# V1_7_7.net
KiCad netlist of a schematic drawn in EAGLE
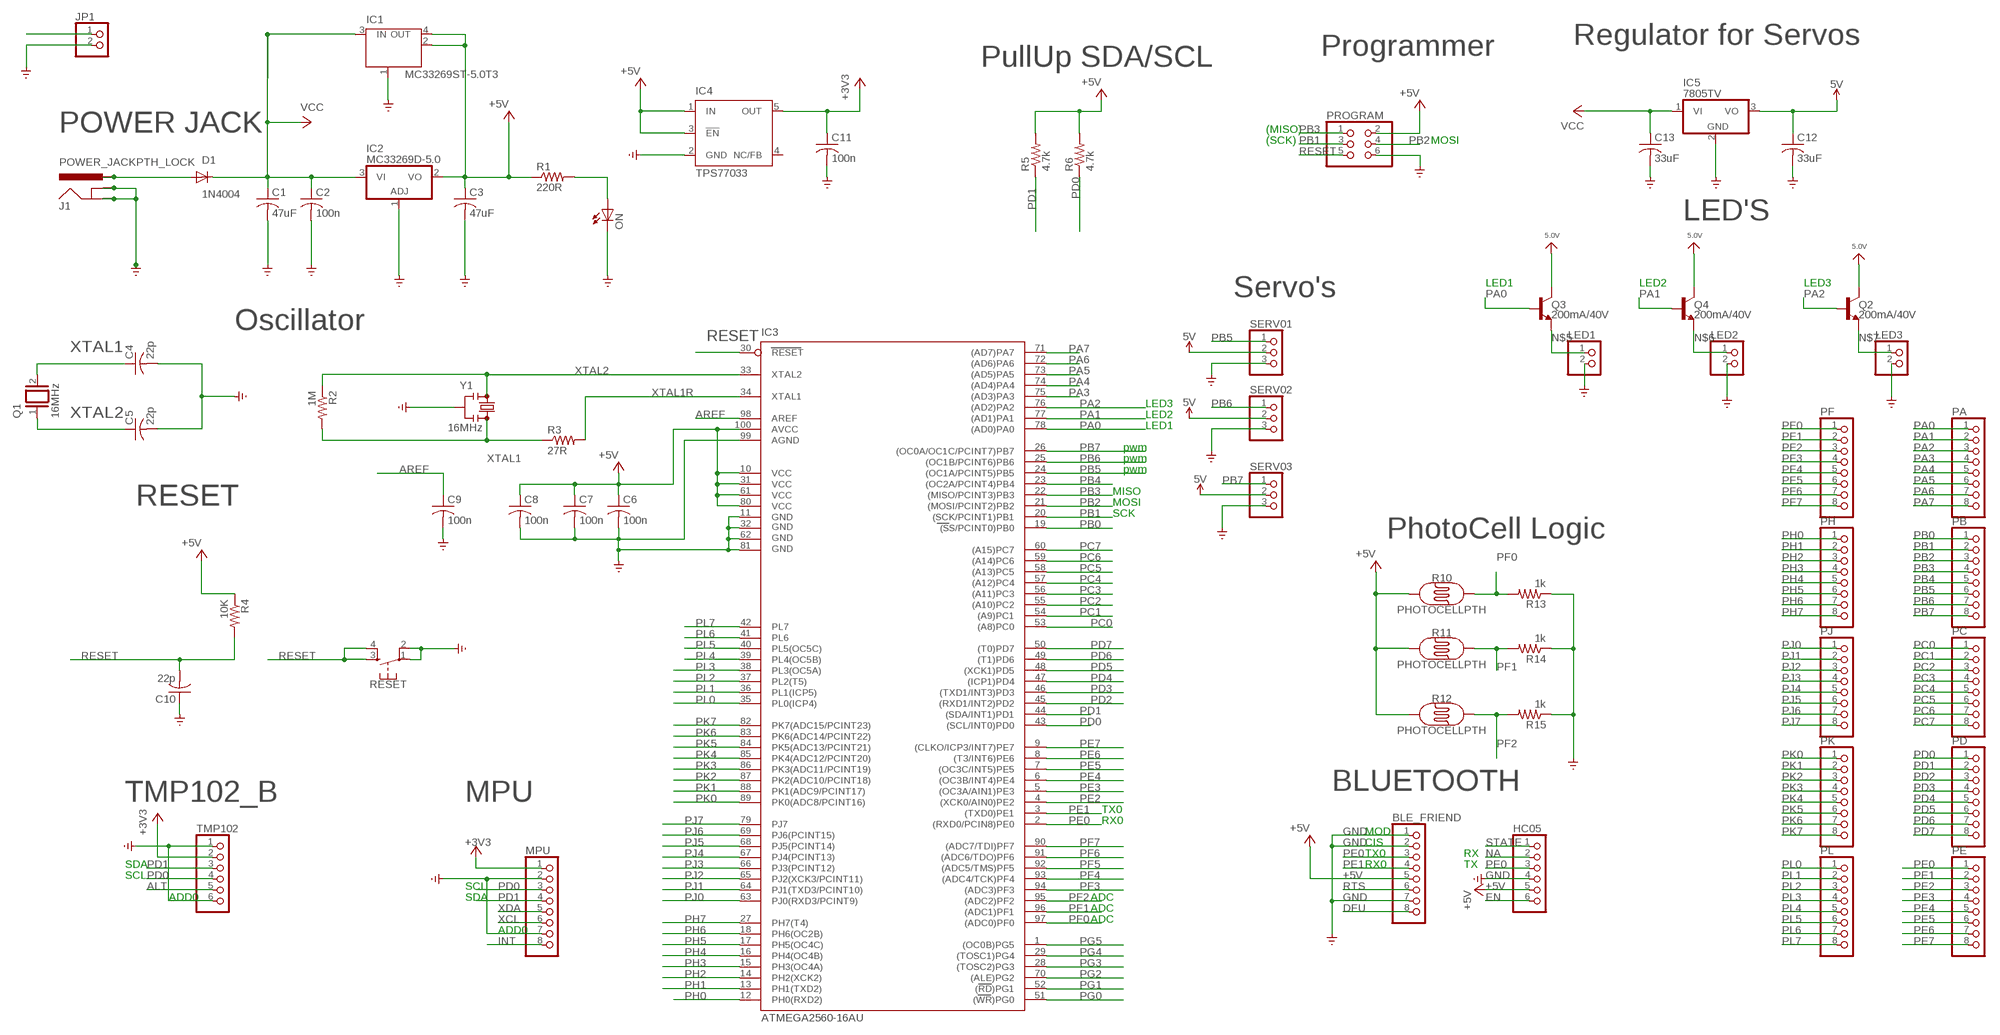
[diagram p0: schematic, sheet 1, part 1 of 2]
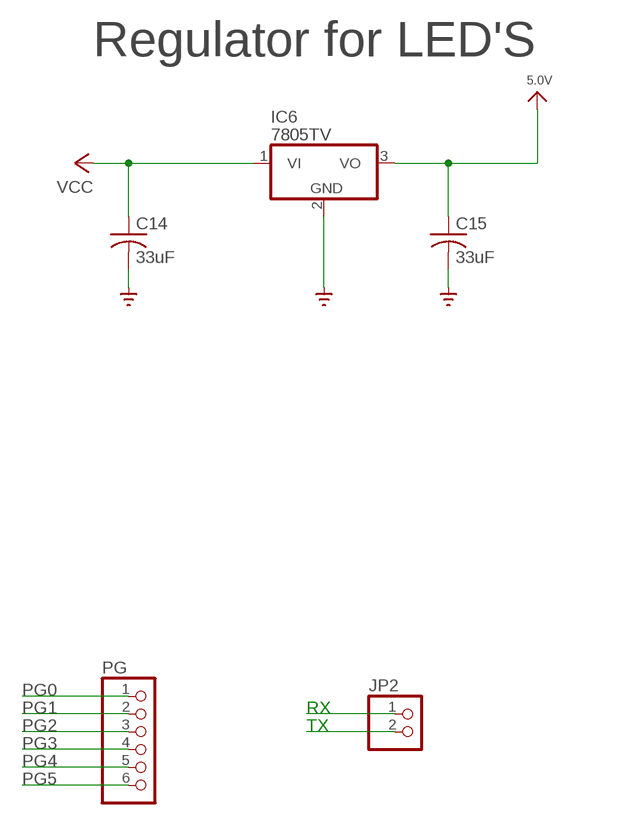
[diagram p1: schematic, sheet 1, part 2 of 2]

(export (version "E")
  (design (tool "Eeschema 10.0.6"))
  (components
    (comp (ref "BLE_FRIEND")
      (value "PINHD-1X8")
      (footprint "eagle-import:1X08")
      (libsource (lib "eagle-import") (part "PINHD-1X8"))
    )
    (comp (ref "C1")
      (value "47uF")
      (footprint "eagle-import:C025-024X044")
      (libsource (lib "eagle-import") (part "C-US025-024X044"))
    )
    (comp (ref "C2")
      (value "100n")
      (footprint "eagle-import:C025-024X044")
      (libsource (lib "eagle-import") (part "C-US025-024X044"))
    )
    (comp (ref "C3")
      (value "47uF")
      (footprint "eagle-import:C025-024X044")
      (libsource (lib "eagle-import") (part "C-US025-024X044"))
    )
    (comp (ref "C4")
      (value "22p")
      (footprint "eagle-import:C025-024X044")
      (libsource (lib "eagle-import") (part "C-US025-024X044"))
    )
    (comp (ref "C5")
      (value "22p")
      (footprint "eagle-import:C025-024X044")
      (libsource (lib "eagle-import") (part "C-US025-024X044"))
    )
    (comp (ref "C6")
      (value "100n")
      (footprint "eagle-import:C025-024X044")
      (libsource (lib "eagle-import") (part "C-US025-024X044"))
    )
    (comp (ref "C7")
      (value "100n")
      (footprint "eagle-import:C025-024X044")
      (libsource (lib "eagle-import") (part "C-US025-024X044"))
    )
    (comp (ref "C8")
      (value "100n")
      (footprint "eagle-import:C025-024X044")
      (libsource (lib "eagle-import") (part "C-US025-024X044"))
    )
    (comp (ref "C9")
      (value "100n")
      (footprint "eagle-import:C025-024X044")
      (libsource (lib "eagle-import") (part "C-US025-024X044"))
    )
    (comp (ref "C10")
      (value "22p")
      (footprint "eagle-import:C025-024X044")
      (libsource (lib "eagle-import") (part "C-US025-024X044"))
    )
    (comp (ref "C11")
      (value "100n")
      (footprint "eagle-import:C025-024X044")
      (libsource (lib "eagle-import") (part "C-US025-024X044"))
    )
    (comp (ref "C12")
      (value "33uF")
      (footprint "eagle-import:C025-024X044")
      (libsource (lib "eagle-import") (part "C-US025-024X044"))
    )
    (comp (ref "C13")
      (value "33uF")
      (footprint "eagle-import:C025-024X044")
      (libsource (lib "eagle-import") (part "C-US025-024X044"))
    )
    (comp (ref "C14")
      (value "33uF")
      (footprint "eagle-import:C025-024X044")
      (libsource (lib "eagle-import") (part "C-US025-024X044"))
    )
    (comp (ref "C15")
      (value "33uF")
      (footprint "eagle-import:C025-024X044")
      (libsource (lib "eagle-import") (part "C-US025-024X044"))
    )
    (comp (ref "D1")
      (value "1N4004")
      (footprint "eagle-import:DO41-10")
      (libsource (lib "eagle-import") (part "1N4004"))
    )
    (comp (ref "HC05")
      (value "PINHD-1X6")
      (footprint "eagle-import:1X06")
      (libsource (lib "eagle-import") (part "pinhead@1_PINHD-1X6"))
    )
    (comp (ref "IC1")
      (value "MC33269ST-5.0T3")
      (footprint "eagle-import:SOT223")
      (libsource (lib "eagle-import") (part "MC33269ST-3.3T3"))
    )
    (comp (ref "IC2")
      (value "MC33269D-5.0")
      (footprint "eagle-import:DPACK")
      (libsource (lib "eagle-import") (part "MC33269?D-5.0"))
    )
    (comp (ref "IC3")
      (value "ATMEGA2560-16AU")
      (footprint "eagle-import:TQFP100")
      (libsource (lib "eagle-import") (part "ATMEGAAU2560-16"))
    )
    (comp (ref "IC4")
      (value "TPS77033")
      (footprint "eagle-import:SOT23-DBV")
      (fields (field (name "MF") "TEXAS INSTRUMENTS") (field (name "MPN") "TPS77033DBVT"))
      (libsource (lib "eagle-import") (part "TPS77033"))
    )
    (comp (ref "IC5")
      (value "7805TV")
      (footprint "eagle-import:TO220V")
      (libsource (lib "eagle-import") (part "78TV05"))
    )
    (comp (ref "IC6")
      (value "7805TV")
      (footprint "eagle-import:TO220V")
      (libsource (lib "eagle-import") (part "78TV05"))
    )
    (comp (ref "J1")
      (value "POWER_JACKPTH_LOCK")
      (footprint "eagle-import:POWER_JACK_PTH_LOCK")
      (libsource (lib "eagle-import") (part "POWER_JACKPTH_LOCK"))
    )
    (comp (ref "JP1")
      (value "PINHD-1X2")
      (footprint "eagle-import:1X02")
      (libsource (lib "eagle-import") (part "PINHD-1X2"))
    )
    (comp (ref "JP2")
      (value "PINHD-1X2")
      (footprint "eagle-import:1X02")
      (libsource (lib "eagle-import") (part "pinhead@1_PINHD-1X2"))
    )
    (comp (ref "LED1")
      (value "PINHD-1X2")
      (footprint "eagle-import:1X02")
      (libsource (lib "eagle-import") (part "PINHD-1X2"))
    )
    (comp (ref "LED2")
      (value "PINHD-1X2")
      (footprint "eagle-import:1X02")
      (libsource (lib "eagle-import") (part "PINHD-1X2"))
    )
    (comp (ref "LED3")
      (value "PINHD-1X2")
      (footprint "eagle-import:1X02")
      (libsource (lib "eagle-import") (part "PINHD-1X2"))
    )
    (comp (ref "MPU")
      (value "PINHD-1X8")
      (footprint "eagle-import:1X08")
      (libsource (lib "eagle-import") (part "PINHD-1X8"))
    )
    (comp (ref "ON")
      (value "LED3MM")
      (footprint "eagle-import:LED3MM")
      (libsource (lib "eagle-import") (part "LED3MM"))
    )
    (comp (ref "PA")
      (value "PINHD-1X8")
      (footprint "eagle-import:1X08")
      (libsource (lib "eagle-import") (part "PINHD-1X8"))
    )
    (comp (ref "PB")
      (value "PINHD-1X8")
      (footprint "eagle-import:1X08")
      (libsource (lib "eagle-import") (part "PINHD-1X8"))
    )
    (comp (ref "PC")
      (value "PINHD-1X8")
      (footprint "eagle-import:1X08")
      (libsource (lib "eagle-import") (part "PINHD-1X8"))
    )
    (comp (ref "PD")
      (value "PINHD-1X8")
      (footprint "eagle-import:1X08")
      (libsource (lib "eagle-import") (part "PINHD-1X8"))
    )
    (comp (ref "PE")
      (value "PINHD-1X8")
      (footprint "eagle-import:1X08")
      (libsource (lib "eagle-import") (part "PINHD-1X8"))
    )
    (comp (ref "PF")
      (value "PINHD-1X8")
      (footprint "eagle-import:1X08")
      (libsource (lib "eagle-import") (part "PINHD-1X8"))
    )
    (comp (ref "PG")
      (value "PINHD-1X6")
      (footprint "eagle-import:1X06")
      (libsource (lib "eagle-import") (part "PINHD-1X6"))
    )
    (comp (ref "PH")
      (value "PINHD-1X8")
      (footprint "eagle-import:1X08")
      (libsource (lib "eagle-import") (part "PINHD-1X8"))
    )
    (comp (ref "PJ")
      (value "PINHD-1X8")
      (footprint "eagle-import:1X08")
      (libsource (lib "eagle-import") (part "PINHD-1X8"))
    )
    (comp (ref "PK")
      (value "PINHD-1X8")
      (footprint "eagle-import:1X08")
      (libsource (lib "eagle-import") (part "PINHD-1X8"))
    )
    (comp (ref "PL")
      (value "PINHD-1X8")
      (footprint "eagle-import:1X08")
      (libsource (lib "eagle-import") (part "PINHD-1X8"))
    )
    (comp (ref "PROGRAM")
      (value "PINHD-2X3")
      (footprint "eagle-import:2X03")
      (libsource (lib "eagle-import") (part "PINHD-2X3"))
    )
    (comp (ref "Q1")
      (value "16MHz")
      (footprint "eagle-import:QS")
      (libsource (lib "eagle-import") (part "XTAL/S"))
    )
    (comp (ref "Q2")
      (value "200mA/40V")
      (footprint "eagle-import:TO-92")
      (libsource (lib "eagle-import") (part "TRANS_NPN-2N3904"))
    )
    (comp (ref "Q3")
      (value "200mA/40V")
      (footprint "eagle-import:TO-92")
      (libsource (lib "eagle-import") (part "TRANS_NPN-2N3904"))
    )
    (comp (ref "Q4")
      (value "200mA/40V")
      (footprint "eagle-import:TO-92")
      (libsource (lib "eagle-import") (part "TRANS_NPN-2N3904"))
    )
    (comp (ref "R1")
      (value "220R")
      (footprint "eagle-import:0204V")
      (libsource (lib "eagle-import") (part "R-US_0204/2V"))
    )
    (comp (ref "R2")
      (value "1M")
      (footprint "eagle-import:0204V")
      (libsource (lib "eagle-import") (part "R-US_0204/2V"))
    )
    (comp (ref "R3")
      (value "27R")
      (footprint "eagle-import:0204V")
      (libsource (lib "eagle-import") (part "R-US_0204/2V"))
    )
    (comp (ref "R4")
      (value "10K")
      (footprint "eagle-import:0204V")
      (libsource (lib "eagle-import") (part "R-US_0204/2V"))
    )
    (comp (ref "R5")
      (value "4.7k")
      (footprint "eagle-import:0204V")
      (libsource (lib "eagle-import") (part "R-US_0204/2V"))
    )
    (comp (ref "R6")
      (value "4.7k")
      (footprint "eagle-import:0204V")
      (libsource (lib "eagle-import") (part "R-US_0204/2V"))
    )
    (comp (ref "R10")
      (value "PHOTOCELLPTH")
      (footprint "eagle-import:PHOTOCELL")
      (libsource (lib "eagle-import") (part "PHOTOCELLPTH"))
    )
    (comp (ref "R11")
      (value "PHOTOCELLPTH")
      (footprint "eagle-import:PHOTOCELL")
      (libsource (lib "eagle-import") (part "PHOTOCELLPTH"))
    )
    (comp (ref "R12")
      (value "PHOTOCELLPTH")
      (footprint "eagle-import:PHOTOCELL")
      (libsource (lib "eagle-import") (part "PHOTOCELLPTH"))
    )
    (comp (ref "R13")
      (value "1k")
      (footprint "eagle-import:0204V")
      (libsource (lib "eagle-import") (part "R-US_0204/2V"))
    )
    (comp (ref "R14")
      (value "1k")
      (footprint "eagle-import:0204V")
      (libsource (lib "eagle-import") (part "R-US_0204/2V"))
    )
    (comp (ref "R15")
      (value "1k")
      (footprint "eagle-import:0204V")
      (libsource (lib "eagle-import") (part "R-US_0204/2V"))
    )
    (comp (ref "RESET")
      (value "MOMENTARY-SWITCH-SPST-2-SMD-5.2MM")
      (footprint "eagle-import:TACTILE_SWITCH_SMD_5.2MM")
      (libsource (lib "eagle-import") (part "MOMENTARY-SWITCH-SPST-2-SMD-5.2MM"))
    )
    (comp (ref "SERV01")
      (value "PINHD-1X3")
      (footprint "eagle-import:1X03")
      (libsource (lib "eagle-import") (part "PINHD-1X3"))
    )
    (comp (ref "SERV02")
      (value "PINHD-1X3")
      (footprint "eagle-import:1X03")
      (libsource (lib "eagle-import") (part "PINHD-1X3"))
    )
    (comp (ref "SERV03")
      (value "PINHD-1X3")
      (footprint "eagle-import:1X03")
      (libsource (lib "eagle-import") (part "PINHD-1X3"))
    )
    (comp (ref "TMP102")
      (value "PINHD-1X6")
      (footprint "eagle-import:1X06")
      (libsource (lib "eagle-import") (part "PINHD-1X6"))
    )
    (comp (ref "Y1")
      (value "16MHz")
      (footprint "eagle-import:RESONATOR-SMD-3.2X1.3")
      (libsource (lib "eagle-import") (part "RESONATORSMD-3.2X1.3"))
    )
  )
  (nets
    (net (code "1") (name "+3V3") (class "Default")
      (node (ref "C11") (pin "1") (pinfunction "1_1") (pintype "passive"))
      (node (ref "IC4") (pin "5") (pinfunction "OUT_5") (pintype "passive"))
      (node (ref "MPU") (pin "1") (pinfunction "1_1") (pintype "passive"))
      (node (ref "TMP102") (pin "2") (pinfunction "2_2") (pintype "passive"))
    )
    (net (code "2") (name "+5V") (class "Default")
      (node (ref "BLE_FRIEND") (pin "5") (pinfunction "5_5") (pintype "passive"))
      (node (ref "C3") (pin "1") (pinfunction "1_1") (pintype "passive"))
      (node (ref "C6") (pin "1") (pinfunction "1_1") (pintype "passive"))
      (node (ref "C7") (pin "1") (pinfunction "1_1") (pintype "passive"))
      (node (ref "C8") (pin "1") (pinfunction "1_1") (pintype "passive"))
      (node (ref "HC05") (pin "5") (pinfunction "5_5") (pintype "passive"))
      (node (ref "IC1") (pin "2") (pinfunction "OUT_2") (pintype "passive"))
      (node (ref "IC1") (pin "4") (pinfunction "OUT_4") (pintype "passive"))
      (node (ref "IC2") (pin "2") (pinfunction "VO_2") (pintype "passive"))
      (node (ref "IC3") (pin "10") (pinfunction "VCC_10") (pintype "power_in"))
      (node (ref "IC3") (pin "100") (pinfunction "AVCC_100") (pintype "power_in"))
      (node (ref "IC3") (pin "31") (pinfunction "VCC1_31") (pintype "power_in"))
      (node (ref "IC3") (pin "61") (pinfunction "VCC2_61") (pintype "power_in"))
      (node (ref "IC3") (pin "80") (pinfunction "VCC3_80") (pintype "power_in"))
      (node (ref "IC4") (pin "1") (pinfunction "IN_1") (pintype "input"))
      (node (ref "IC4") (pin "3") (pinfunction "~{EN}_3") (pintype "input"))
      (node (ref "PROGRAM") (pin "2") (pinfunction "2_2") (pintype "passive"))
      (node (ref "R1") (pin "1") (pinfunction "1_1") (pintype "passive"))
      (node (ref "R10") (pin "1") (pinfunction "P$1_1") (pintype "bidirectional"))
      (node (ref "R11") (pin "1") (pinfunction "P$1_1") (pintype "bidirectional"))
      (node (ref "R12") (pin "1") (pinfunction "P$1_1") (pintype "bidirectional"))
      (node (ref "R4") (pin "1") (pinfunction "1_1") (pintype "passive"))
      (node (ref "R5") (pin "2") (pinfunction "2_2") (pintype "passive"))
      (node (ref "R6") (pin "2") (pinfunction "2_2") (pintype "passive"))
    )
    (net (code "3") (name "/ALT") (class "Default")
      (node (ref "TMP102") (pin "5") (pinfunction "5_5") (pintype "passive"))
    )
    (net (code "4") (name "/AREF") (class "Default")
      (node (ref "C9") (pin "1") (pinfunction "1_1") (pintype "passive"))
      (node (ref "IC3") (pin "98") (pinfunction "AREF_98") (pintype "bidirectional"))
    )
    (net (code "5") (name "/DFU") (class "Default")
      (node (ref "BLE_FRIEND") (pin "8") (pinfunction "8_8") (pintype "passive"))
    )
    (net (code "6") (name "/EN") (class "Default")
      (node (ref "HC05") (pin "6") (pinfunction "6_6") (pintype "passive"))
    )
    (net (code "7") (name "/INT") (class "Default")
      (node (ref "MPU") (pin "8") (pinfunction "8_8") (pintype "passive"))
    )
    (net (code "8") (name "/N$5") (class "Default")
      (node (ref "LED1") (pin "1") (pinfunction "1_1") (pintype "passive"))
      (node (ref "Q3") (pin "1") (pinfunction "E_1") (pintype "passive"))
    )
    (net (code "9") (name "/N$6") (class "Default")
      (node (ref "LED2") (pin "1") (pinfunction "1_1") (pintype "passive"))
      (node (ref "Q4") (pin "1") (pinfunction "E_1") (pintype "passive"))
    )
    (net (code "10") (name "/N$7") (class "Default")
      (node (ref "LED3") (pin "1") (pinfunction "1_1") (pintype "passive"))
      (node (ref "Q2") (pin "1") (pinfunction "E_1") (pintype "passive"))
    )
    (net (code "11") (name "/NA") (class "Default")
      (node (ref "HC05") (pin "2") (pinfunction "2_2") (pintype "passive"))
    )
    (net (code "12") (name "/PA0") (class "Default")
      (node (ref "IC3") (pin "78") (pinfunction "(AD0)PA0_78") (pintype "bidirectional"))
      (node (ref "PA") (pin "1") (pinfunction "1_1") (pintype "passive"))
      (node (ref "Q3") (pin "2") (pinfunction "B_2") (pintype "passive"))
    )
    (net (code "13") (name "/PA1") (class "Default")
      (node (ref "IC3") (pin "77") (pinfunction "(AD1)PA1_77") (pintype "bidirectional"))
      (node (ref "PA") (pin "2") (pinfunction "2_2") (pintype "passive"))
      (node (ref "Q4") (pin "2") (pinfunction "B_2") (pintype "passive"))
    )
    (net (code "14") (name "/PA2") (class "Default")
      (node (ref "IC3") (pin "76") (pinfunction "(AD2)PA2_76") (pintype "bidirectional"))
      (node (ref "PA") (pin "3") (pinfunction "3_3") (pintype "passive"))
      (node (ref "Q2") (pin "2") (pinfunction "B_2") (pintype "passive"))
    )
    (net (code "15") (name "/PA3") (class "Default")
      (node (ref "IC3") (pin "75") (pinfunction "(AD3)PA3_75") (pintype "bidirectional"))
      (node (ref "PA") (pin "4") (pinfunction "4_4") (pintype "passive"))
    )
    (net (code "16") (name "/PA4") (class "Default")
      (node (ref "IC3") (pin "74") (pinfunction "(AD4)PA4_74") (pintype "bidirectional"))
      (node (ref "PA") (pin "5") (pinfunction "5_5") (pintype "passive"))
    )
    (net (code "17") (name "/PA5") (class "Default")
      (node (ref "IC3") (pin "73") (pinfunction "(AD5)PA5_73") (pintype "bidirectional"))
      (node (ref "PA") (pin "6") (pinfunction "6_6") (pintype "passive"))
    )
    (net (code "18") (name "/PA6") (class "Default")
      (node (ref "IC3") (pin "72") (pinfunction "(AD6)PA6_72") (pintype "bidirectional"))
      (node (ref "PA") (pin "7") (pinfunction "7_7") (pintype "passive"))
    )
    (net (code "19") (name "/PA7") (class "Default")
      (node (ref "IC3") (pin "71") (pinfunction "(AD7)PA7_71") (pintype "bidirectional"))
      (node (ref "PA") (pin "8") (pinfunction "8_8") (pintype "passive"))
    )
    (net (code "20") (name "/PB0") (class "Default")
      (node (ref "IC3") (pin "19") (pinfunction "(SS/PCINT0)PB0_19") (pintype "bidirectional"))
      (node (ref "PB") (pin "1") (pinfunction "1_1") (pintype "passive"))
    )
    (net (code "21") (name "/PB1") (class "Default")
      (node (ref "IC3") (pin "20") (pinfunction "(SCK/PCINT1)PB1_20") (pintype "bidirectional"))
      (node (ref "PB") (pin "2") (pinfunction "2_2") (pintype "passive"))
      (node (ref "PROGRAM") (pin "3") (pinfunction "3_3") (pintype "passive"))
    )
    (net (code "22") (name "/PB2") (class "Default")
      (node (ref "IC3") (pin "21") (pinfunction "(MOSI/PCINT2)PB2_21") (pintype "bidirectional"))
      (node (ref "PB") (pin "3") (pinfunction "3_3") (pintype "passive"))
      (node (ref "PROGRAM") (pin "4") (pinfunction "4_4") (pintype "passive"))
    )
    (net (code "23") (name "/PB3") (class "Default")
      (node (ref "IC3") (pin "22") (pinfunction "(MISO/PCINT3)PB3_22") (pintype "bidirectional"))
      (node (ref "PB") (pin "4") (pinfunction "4_4") (pintype "passive"))
      (node (ref "PROGRAM") (pin "1") (pinfunction "1_1") (pintype "passive"))
    )
    (net (code "24") (name "/PB4") (class "Default")
      (node (ref "IC3") (pin "23") (pinfunction "(OC2A/PCINT4)PB4_23") (pintype "bidirectional"))
      (node (ref "PB") (pin "5") (pinfunction "5_5") (pintype "passive"))
    )
    (net (code "25") (name "/PB5") (class "Default")
      (node (ref "IC3") (pin "24") (pinfunction "(OC1A/PCINT5)PB5_24") (pintype "bidirectional"))
      (node (ref "PB") (pin "6") (pinfunction "6_6") (pintype "passive"))
      (node (ref "SERV01") (pin "1") (pinfunction "1_1") (pintype "passive"))
    )
    (net (code "26") (name "/PB6") (class "Default")
      (node (ref "IC3") (pin "25") (pinfunction "(OC1B/PCINT6)PB6_25") (pintype "bidirectional"))
      (node (ref "PB") (pin "7") (pinfunction "7_7") (pintype "passive"))
      (node (ref "SERV02") (pin "1") (pinfunction "1_1") (pintype "passive"))
    )
    (net (code "27") (name "/PB7") (class "Default")
      (node (ref "IC3") (pin "26") (pinfunction "(OC0A/OC1C/PCINT7)PB7_26") (pintype "bidirectional"))
      (node (ref "PB") (pin "8") (pinfunction "8_8") (pintype "passive"))
      (node (ref "SERV03") (pin "1") (pinfunction "1_1") (pintype "passive"))
    )
    (net (code "28") (name "/PC0") (class "Default")
      (node (ref "IC3") (pin "53") (pinfunction "(A8)PC0_53") (pintype "bidirectional"))
      (node (ref "PC") (pin "1") (pinfunction "1_1") (pintype "passive"))
    )
    (net (code "29") (name "/PC1") (class "Default")
      (node (ref "IC3") (pin "54") (pinfunction "(A9)PC1_54") (pintype "bidirectional"))
      (node (ref "PC") (pin "2") (pinfunction "2_2") (pintype "passive"))
    )
    (net (code "30") (name "/PC2") (class "Default")
      (node (ref "IC3") (pin "55") (pinfunction "(A10)PC2_55") (pintype "bidirectional"))
      (node (ref "PC") (pin "3") (pinfunction "3_3") (pintype "passive"))
    )
    (net (code "31") (name "/PC3") (class "Default")
      (node (ref "IC3") (pin "56") (pinfunction "(A11)PC3_56") (pintype "bidirectional"))
      (node (ref "PC") (pin "4") (pinfunction "4_4") (pintype "passive"))
    )
    (net (code "32") (name "/PC4") (class "Default")
      (node (ref "IC3") (pin "57") (pinfunction "(A12)PC4_57") (pintype "bidirectional"))
      (node (ref "PC") (pin "5") (pinfunction "5_5") (pintype "passive"))
    )
    (net (code "33") (name "/PC5") (class "Default")
      (node (ref "IC3") (pin "58") (pinfunction "(A13)PC5_58") (pintype "bidirectional"))
      (node (ref "PC") (pin "6") (pinfunction "6_6") (pintype "passive"))
    )
    (net (code "34") (name "/PC6") (class "Default")
      (node (ref "IC3") (pin "59") (pinfunction "(A14)PC6_59") (pintype "bidirectional"))
      (node (ref "PC") (pin "7") (pinfunction "7_7") (pintype "passive"))
    )
    (net (code "35") (name "/PC7") (class "Default")
      (node (ref "IC3") (pin "60") (pinfunction "(A15)PC7_60") (pintype "bidirectional"))
      (node (ref "PC") (pin "8") (pinfunction "8_8") (pintype "passive"))
    )
    (net (code "36") (name "/PD0") (class "Default")
      (node (ref "IC3") (pin "43") (pinfunction "(SCL/INT0)PD0_43") (pintype "bidirectional"))
      (node (ref "MPU") (pin "3") (pinfunction "3_3") (pintype "passive"))
      (node (ref "PD") (pin "1") (pinfunction "1_1") (pintype "passive"))
      (node (ref "R6") (pin "1") (pinfunction "1_1") (pintype "passive"))
      (node (ref "TMP102") (pin "4") (pinfunction "4_4") (pintype "passive"))
    )
    (net (code "37") (name "/PD1") (class "Default")
      (node (ref "IC3") (pin "44") (pinfunction "(SDA/INT1)PD1_44") (pintype "bidirectional"))
      (node (ref "MPU") (pin "4") (pinfunction "4_4") (pintype "passive"))
      (node (ref "PD") (pin "2") (pinfunction "2_2") (pintype "passive"))
      (node (ref "R5") (pin "1") (pinfunction "1_1") (pintype "passive"))
      (node (ref "TMP102") (pin "3") (pinfunction "3_3") (pintype "passive"))
    )
    (net (code "38") (name "/PD2") (class "Default")
      (node (ref "IC3") (pin "45") (pinfunction "(RXD1/INT2)PD2_45") (pintype "bidirectional"))
      (node (ref "PD") (pin "3") (pinfunction "3_3") (pintype "passive"))
    )
    (net (code "39") (name "/PD3") (class "Default")
      (node (ref "IC3") (pin "46") (pinfunction "(TXD1/INT3)PD3_46") (pintype "bidirectional"))
      (node (ref "PD") (pin "4") (pinfunction "4_4") (pintype "passive"))
    )
    (net (code "40") (name "/PD4") (class "Default")
      (node (ref "IC3") (pin "47") (pinfunction "(ICP1)PD4_47") (pintype "bidirectional"))
      (node (ref "PD") (pin "5") (pinfunction "5_5") (pintype "passive"))
    )
    (net (code "41") (name "/PD5") (class "Default")
      (node (ref "IC3") (pin "48") (pinfunction "(XCK1)PD5_48") (pintype "bidirectional"))
      (node (ref "PD") (pin "6") (pinfunction "6_6") (pintype "passive"))
    )
    (net (code "42") (name "/PD6") (class "Default")
      (node (ref "IC3") (pin "49") (pinfunction "(T1)PD6_49") (pintype "bidirectional"))
      (node (ref "PD") (pin "7") (pinfunction "7_7") (pintype "passive"))
    )
    (net (code "43") (name "/PD7") (class "Default")
      (node (ref "IC3") (pin "50") (pinfunction "(T0)PD7_50") (pintype "bidirectional"))
      (node (ref "PD") (pin "8") (pinfunction "8_8") (pintype "passive"))
    )
    (net (code "44") (name "/PE0") (class "Default")
      (node (ref "BLE_FRIEND") (pin "3") (pinfunction "3_3") (pintype "passive"))
      (node (ref "HC05") (pin "3") (pinfunction "3_3") (pintype "passive"))
      (node (ref "IC3") (pin "2") (pinfunction "(RXD0/PCIN8)PE0_2") (pintype "bidirectional"))
      (node (ref "JP2") (pin "1") (pinfunction "1_1") (pintype "passive"))
      (node (ref "PE") (pin "1") (pinfunction "1_1") (pintype "passive"))
    )
    (net (code "45") (name "/PE1") (class "Default")
      (node (ref "BLE_FRIEND") (pin "4") (pinfunction "4_4") (pintype "passive"))
      (node (ref "IC3") (pin "3") (pinfunction "(TXD0)PE1_3") (pintype "bidirectional"))
      (node (ref "JP2") (pin "2") (pinfunction "2_2") (pintype "passive"))
      (node (ref "PE") (pin "2") (pinfunction "2_2") (pintype "passive"))
    )
    (net (code "46") (name "/PE2") (class "Default")
      (node (ref "IC3") (pin "4") (pinfunction "(XCK0/AIN0)PE2_4") (pintype "bidirectional"))
      (node (ref "PE") (pin "3") (pinfunction "3_3") (pintype "passive"))
    )
    (net (code "47") (name "/PE3") (class "Default")
      (node (ref "IC3") (pin "5") (pinfunction "(OC3A/AIN1)PE3_5") (pintype "bidirectional"))
      (node (ref "PE") (pin "4") (pinfunction "4_4") (pintype "passive"))
    )
    (net (code "48") (name "/PE4") (class "Default")
      (node (ref "IC3") (pin "6") (pinfunction "(OC3B/INT4)PE4_6") (pintype "bidirectional"))
      (node (ref "PE") (pin "5") (pinfunction "5_5") (pintype "passive"))
    )
    (net (code "49") (name "/PE5") (class "Default")
      (node (ref "IC3") (pin "7") (pinfunction "(OC3C/INT5)PE5_7") (pintype "bidirectional"))
      (node (ref "PE") (pin "6") (pinfunction "6_6") (pintype "passive"))
    )
    (net (code "50") (name "/PE6") (class "Default")
      (node (ref "IC3") (pin "8") (pinfunction "(T3/INT6)PE6_8") (pintype "bidirectional"))
      (node (ref "PE") (pin "7") (pinfunction "7_7") (pintype "passive"))
    )
    (net (code "51") (name "/PE7") (class "Default")
      (node (ref "IC3") (pin "9") (pinfunction "(CLKO/ICP3/INT7)PE7_9") (pintype "bidirectional"))
      (node (ref "PE") (pin "8") (pinfunction "8_8") (pintype "passive"))
    )
    (net (code "52") (name "/PF0") (class "Default")
      (node (ref "IC3") (pin "97") (pinfunction "(ADC0)PF0_97") (pintype "bidirectional"))
      (node (ref "PF") (pin "1") (pinfunction "1_1") (pintype "passive"))
      (node (ref "R10") (pin "2") (pinfunction "P$2_2") (pintype "bidirectional"))
      (node (ref "R13") (pin "2") (pinfunction "2_2") (pintype "passive"))
    )
    (net (code "53") (name "/PF1") (class "Default")
      (node (ref "IC3") (pin "96") (pinfunction "(ADC1)PF1_96") (pintype "bidirectional"))
      (node (ref "PF") (pin "2") (pinfunction "2_2") (pintype "passive"))
      (node (ref "R11") (pin "2") (pinfunction "P$2_2") (pintype "bidirectional"))
      (node (ref "R14") (pin "2") (pinfunction "2_2") (pintype "passive"))
    )
    (net (code "54") (name "/PF2") (class "Default")
      (node (ref "IC3") (pin "95") (pinfunction "(ADC2)PF2_95") (pintype "bidirectional"))
      (node (ref "PF") (pin "3") (pinfunction "3_3") (pintype "passive"))
      (node (ref "R12") (pin "2") (pinfunction "P$2_2") (pintype "bidirectional"))
      (node (ref "R15") (pin "2") (pinfunction "2_2") (pintype "passive"))
    )
    (net (code "55") (name "/PF3") (class "Default")
      (node (ref "IC3") (pin "94") (pinfunction "(ADC3)PF3_94") (pintype "bidirectional"))
      (node (ref "PF") (pin "4") (pinfunction "4_4") (pintype "passive"))
    )
    (net (code "56") (name "/PF4") (class "Default")
      (node (ref "IC3") (pin "93") (pinfunction "(ADC4/TCK)PF4_93") (pintype "bidirectional"))
      (node (ref "PF") (pin "5") (pinfunction "5_5") (pintype "passive"))
    )
    (net (code "57") (name "/PF5") (class "Default")
      (node (ref "IC3") (pin "92") (pinfunction "(ADC5/TMS)PF5_92") (pintype "bidirectional"))
      (node (ref "PF") (pin "6") (pinfunction "6_6") (pintype "passive"))
    )
    (net (code "58") (name "/PF6") (class "Default")
      (node (ref "IC3") (pin "91") (pinfunction "(ADC6/TDO)PF6_91") (pintype "bidirectional"))
      (node (ref "PF") (pin "7") (pinfunction "7_7") (pintype "passive"))
    )
    (net (code "59") (name "/PF7") (class "Default")
      (node (ref "IC3") (pin "90") (pinfunction "(ADC7/TDI)PF7_90") (pintype "bidirectional"))
      (node (ref "PF") (pin "8") (pinfunction "8_8") (pintype "passive"))
    )
    (net (code "60") (name "/PG0") (class "Default")
      (node (ref "IC3") (pin "51") (pinfunction "(WR)PG0_51") (pintype "bidirectional"))
      (node (ref "PG") (pin "1") (pinfunction "1_1") (pintype "passive"))
    )
    (net (code "61") (name "/PG1") (class "Default")
      (node (ref "IC3") (pin "52") (pinfunction "(RD)PG1_52") (pintype "bidirectional"))
      (node (ref "PG") (pin "2") (pinfunction "2_2") (pintype "passive"))
    )
    (net (code "62") (name "/PG2") (class "Default")
      (node (ref "IC3") (pin "70") (pinfunction "(ALE)PG2_70") (pintype "bidirectional"))
      (node (ref "PG") (pin "3") (pinfunction "3_3") (pintype "passive"))
    )
    (net (code "63") (name "/PG3") (class "Default")
      (node (ref "IC3") (pin "28") (pinfunction "(TOSC2)PG3_28") (pintype "bidirectional"))
      (node (ref "PG") (pin "4") (pinfunction "4_4") (pintype "passive"))
    )
    (net (code "64") (name "/PG4") (class "Default")
      (node (ref "IC3") (pin "29") (pinfunction "(TOSC1)PG4_29") (pintype "bidirectional"))
      (node (ref "PG") (pin "5") (pinfunction "5_5") (pintype "passive"))
    )
    (net (code "65") (name "/PG5") (class "Default")
      (node (ref "IC3") (pin "1") (pinfunction "(OC0B)PG5_1") (pintype "bidirectional"))
      (node (ref "PG") (pin "6") (pinfunction "6_6") (pintype "passive"))
    )
    (net (code "66") (name "/PH0") (class "Default")
      (node (ref "IC3") (pin "12") (pinfunction "PH0(RXD2)_12") (pintype "bidirectional"))
      (node (ref "PH") (pin "1") (pinfunction "1_1") (pintype "passive"))
    )
    (net (code "67") (name "/PH1") (class "Default")
      (node (ref "IC3") (pin "13") (pinfunction "PH1(TXD2)_13") (pintype "bidirectional"))
      (node (ref "PH") (pin "2") (pinfunction "2_2") (pintype "passive"))
    )
    (net (code "68") (name "/PH2") (class "Default")
      (node (ref "IC3") (pin "14") (pinfunction "PH2(XCK2)_14") (pintype "bidirectional"))
      (node (ref "PH") (pin "3") (pinfunction "3_3") (pintype "passive"))
    )
    (net (code "69") (name "/PH3") (class "Default")
      (node (ref "IC3") (pin "15") (pinfunction "PH3(OC4A)_15") (pintype "bidirectional"))
      (node (ref "PH") (pin "4") (pinfunction "4_4") (pintype "passive"))
    )
    (net (code "70") (name "/PH4") (class "Default")
      (node (ref "IC3") (pin "16") (pinfunction "PH4(OC4B)_16") (pintype "bidirectional"))
      (node (ref "PH") (pin "5") (pinfunction "5_5") (pintype "passive"))
    )
    (net (code "71") (name "/PH5") (class "Default")
      (node (ref "IC3") (pin "17") (pinfunction "PH5(OC4C)_17") (pintype "bidirectional"))
      (node (ref "PH") (pin "6") (pinfunction "6_6") (pintype "passive"))
    )
    (net (code "72") (name "/PH6") (class "Default")
      (node (ref "IC3") (pin "18") (pinfunction "PH6(OC2B)_18") (pintype "bidirectional"))
      (node (ref "PH") (pin "7") (pinfunction "7_7") (pintype "passive"))
    )
    (net (code "73") (name "/PH7") (class "Default")
      (node (ref "IC3") (pin "27") (pinfunction "PH7(T4)_27") (pintype "bidirectional"))
      (node (ref "PH") (pin "8") (pinfunction "8_8") (pintype "passive"))
    )
    (net (code "74") (name "/PJ0") (class "Default")
      (node (ref "IC3") (pin "63") (pinfunction "PJ0(RXD3/PCINT9)_63") (pintype "bidirectional"))
      (node (ref "PJ") (pin "1") (pinfunction "1_1") (pintype "passive"))
    )
    (net (code "75") (name "/PJ1") (class "Default")
      (node (ref "IC3") (pin "64") (pinfunction "PJ1(TXD3/PCINT10)_64") (pintype "bidirectional"))
      (node (ref "PJ") (pin "2") (pinfunction "2_2") (pintype "passive"))
    )
    (net (code "76") (name "/PJ2") (class "Default")
      (node (ref "IC3") (pin "65") (pinfunction "PJ2(XCK3/PCINT11)_65") (pintype "bidirectional"))
      (node (ref "PJ") (pin "3") (pinfunction "3_3") (pintype "passive"))
    )
    (net (code "77") (name "/PJ3") (class "Default")
      (node (ref "IC3") (pin "66") (pinfunction "PJ3(PCINT12)_66") (pintype "bidirectional"))
      (node (ref "PJ") (pin "4") (pinfunction "4_4") (pintype "passive"))
    )
    (net (code "78") (name "/PJ4") (class "Default")
      (node (ref "IC3") (pin "67") (pinfunction "PJ4(PCINT13)_67") (pintype "bidirectional"))
      (node (ref "PJ") (pin "5") (pinfunction "5_5") (pintype "passive"))
    )
    (net (code "79") (name "/PJ5") (class "Default")
      (node (ref "IC3") (pin "68") (pinfunction "PJ5(PCINT14)_68") (pintype "bidirectional"))
      (node (ref "PJ") (pin "6") (pinfunction "6_6") (pintype "passive"))
    )
    (net (code "80") (name "/PJ6") (class "Default")
      (node (ref "IC3") (pin "69") (pinfunction "PJ6(PCINT15)_69") (pintype "bidirectional"))
      (node (ref "PJ") (pin "7") (pinfunction "7_7") (pintype "passive"))
    )
    (net (code "81") (name "/PJ7") (class "Default")
      (node (ref "IC3") (pin "79") (pinfunction "PJ7_79") (pintype "bidirectional"))
      (node (ref "PJ") (pin "8") (pinfunction "8_8") (pintype "passive"))
    )
    (net (code "82") (name "/PK0") (class "Default")
      (node (ref "IC3") (pin "89") (pinfunction "PK0(ADC8/PCINT16)_89") (pintype "bidirectional"))
      (node (ref "PK") (pin "1") (pinfunction "1_1") (pintype "passive"))
    )
    (net (code "83") (name "/PK1") (class "Default")
      (node (ref "IC3") (pin "88") (pinfunction "PK1(ADC9/PCINT17)_88") (pintype "bidirectional"))
      (node (ref "PK") (pin "2") (pinfunction "2_2") (pintype "passive"))
    )
    (net (code "84") (name "/PK2") (class "Default")
      (node (ref "IC3") (pin "87") (pinfunction "PK2(ADC10/PCINT18)_87") (pintype "bidirectional"))
      (node (ref "PK") (pin "3") (pinfunction "3_3") (pintype "passive"))
    )
    (net (code "85") (name "/PK3") (class "Default")
      (node (ref "IC3") (pin "86") (pinfunction "PK3(ADC11/PCINT19)_86") (pintype "bidirectional"))
      (node (ref "PK") (pin "4") (pinfunction "4_4") (pintype "passive"))
    )
    (net (code "86") (name "/PK4") (class "Default")
      (node (ref "IC3") (pin "85") (pinfunction "PK4(ADC12/PCINT20)_85") (pintype "bidirectional"))
      (node (ref "PK") (pin "5") (pinfunction "5_5") (pintype "passive"))
    )
    (net (code "87") (name "/PK5") (class "Default")
      (node (ref "IC3") (pin "84") (pinfunction "PK5(ADC13/PCINT21)_84") (pintype "bidirectional"))
      (node (ref "PK") (pin "6") (pinfunction "6_6") (pintype "passive"))
    )
    (net (code "88") (name "/PK6") (class "Default")
      (node (ref "IC3") (pin "83") (pinfunction "PK6(ADC14/PCINT22)_83") (pintype "bidirectional"))
      (node (ref "PK") (pin "7") (pinfunction "7_7") (pintype "passive"))
    )
    (net (code "89") (name "/PK7") (class "Default")
      (node (ref "IC3") (pin "82") (pinfunction "PK7(ADC15/PCINT23)_82") (pintype "bidirectional"))
      (node (ref "PK") (pin "8") (pinfunction "8_8") (pintype "passive"))
    )
    (net (code "90") (name "/PL0") (class "Default")
      (node (ref "IC3") (pin "35") (pinfunction "PL0(ICP4)_35") (pintype "bidirectional"))
      (node (ref "PL") (pin "1") (pinfunction "1_1") (pintype "passive"))
    )
    (net (code "91") (name "/PL1") (class "Default")
      (node (ref "IC3") (pin "36") (pinfunction "PL1(ICP5)_36") (pintype "bidirectional"))
      (node (ref "PL") (pin "2") (pinfunction "2_2") (pintype "passive"))
    )
    (net (code "92") (name "/PL2") (class "Default")
      (node (ref "IC3") (pin "37") (pinfunction "PL2(T5)_37") (pintype "bidirectional"))
      (node (ref "PL") (pin "3") (pinfunction "3_3") (pintype "passive"))
    )
    (net (code "93") (name "/PL3") (class "Default")
      (node (ref "IC3") (pin "38") (pinfunction "PL3(OC5A)_38") (pintype "bidirectional"))
      (node (ref "PL") (pin "4") (pinfunction "4_4") (pintype "passive"))
    )
    (net (code "94") (name "/PL4") (class "Default")
      (node (ref "IC3") (pin "39") (pinfunction "PL4(OC5B)_39") (pintype "bidirectional"))
      (node (ref "PL") (pin "5") (pinfunction "5_5") (pintype "passive"))
    )
    (net (code "95") (name "/PL5") (class "Default")
      (node (ref "IC3") (pin "40") (pinfunction "PL5(OC5C)_40") (pintype "bidirectional"))
      (node (ref "PL") (pin "6") (pinfunction "6_6") (pintype "passive"))
    )
    (net (code "96") (name "/PL6") (class "Default")
      (node (ref "IC3") (pin "41") (pinfunction "PL6_41") (pintype "bidirectional"))
      (node (ref "PL") (pin "7") (pinfunction "7_7") (pintype "passive"))
    )
    (net (code "97") (name "/PL7") (class "Default")
      (node (ref "IC3") (pin "42") (pinfunction "PL7_42") (pintype "bidirectional"))
      (node (ref "PL") (pin "8") (pinfunction "8_8") (pintype "passive"))
    )
    (net (code "98") (name "/POWERIN") (class "Default")
      (node (ref "D1") (pin "A") (pinfunction "A_A") (pintype "passive"))
      (node (ref "J1") (pin "PWR") (pinfunction "PWR_PWR") (pintype "bidirectional"))
      (node (ref "JP1") (pin "1") (pinfunction "1_1") (pintype "passive"))
    )
    (net (code "99") (name "/RESET") (class "Default")
      (node (ref "C10") (pin "2") (pinfunction "2_2") (pintype "passive"))
      (node (ref "IC3") (pin "30") (pinfunction "RESET_30") (pintype "input"))
      (node (ref "PROGRAM") (pin "5") (pinfunction "5_5") (pintype "passive"))
      (node (ref "R4") (pin "2") (pinfunction "2_2") (pintype "passive"))
      (node (ref "RESET") (pin "3") (pinfunction "3_3") (pintype "passive"))
      (node (ref "RESET") (pin "4") (pinfunction "4_4") (pintype "passive"))
    )
    (net (code "100") (name "/RTS") (class "Default")
      (node (ref "BLE_FRIEND") (pin "6") (pinfunction "6_6") (pintype "passive"))
    )
    (net (code "101") (name "/STATE") (class "Default")
      (node (ref "HC05") (pin "1") (pinfunction "1_1") (pintype "passive"))
    )
    (net (code "102") (name "/XCL") (class "Default")
      (node (ref "MPU") (pin "6") (pinfunction "6_6") (pintype "passive"))
    )
    (net (code "103") (name "/XDA") (class "Default")
      (node (ref "MPU") (pin "5") (pinfunction "5_5") (pintype "passive"))
    )
    (net (code "104") (name "/XTAL1") (class "Default")
      (node (ref "C4") (pin "1") (pinfunction "1_1") (pintype "passive"))
      (node (ref "Q1") (pin "2") (pinfunction "2_2") (pintype "passive"))
      (node (ref "R2") (pin "2") (pinfunction "2_2") (pintype "passive"))
      (node (ref "R3") (pin "1") (pinfunction "1_1") (pintype "passive"))
      (node (ref "Y1") (pin "3") (pinfunction "3_3") (pintype "passive"))
    )
    (net (code "105") (name "/XTAL1R") (class "Default")
      (node (ref "IC3") (pin "34") (pinfunction "XTAL1_34") (pintype "input"))
      (node (ref "R3") (pin "2") (pinfunction "2_2") (pintype "passive"))
    )
    (net (code "106") (name "/XTAL2") (class "Default")
      (node (ref "C5") (pin "1") (pinfunction "1_1") (pintype "passive"))
      (node (ref "IC3") (pin "33") (pinfunction "XTAL2_33") (pintype "output"))
      (node (ref "Q1") (pin "1") (pinfunction "1_1") (pintype "passive"))
      (node (ref "R2") (pin "1") (pinfunction "1_1") (pintype "passive"))
      (node (ref "Y1") (pin "1") (pinfunction "1_1") (pintype "passive"))
    )
    (net (code "107") (name "5.0V") (class "Default")
      (node (ref "C15") (pin "1") (pinfunction "1_1") (pintype "passive"))
      (node (ref "IC6") (pin "3") (pinfunction "VO_3") (pintype "passive"))
      (node (ref "Q2") (pin "3") (pinfunction "C_3") (pintype "passive"))
      (node (ref "Q3") (pin "3") (pinfunction "C_3") (pintype "passive"))
      (node (ref "Q4") (pin "3") (pinfunction "C_3") (pintype "passive"))
    )
    (net (code "108") (name "5V") (class "Default")
      (node (ref "C12") (pin "1") (pinfunction "1_1") (pintype "passive"))
      (node (ref "IC5") (pin "3") (pinfunction "VO_3") (pintype "passive"))
      (node (ref "SERV01") (pin "2") (pinfunction "2_2") (pintype "passive"))
      (node (ref "SERV02") (pin "2") (pinfunction "2_2") (pintype "passive"))
      (node (ref "SERV03") (pin "2") (pinfunction "2_2") (pintype "passive"))
    )
    (net (code "109") (name "GND_") (class "Default")
      (node (ref "BLE_FRIEND") (pin "1") (pinfunction "1_1") (pintype "passive"))
      (node (ref "BLE_FRIEND") (pin "2") (pinfunction "2_2") (pintype "passive"))
      (node (ref "BLE_FRIEND") (pin "7") (pinfunction "7_7") (pintype "passive"))
      (node (ref "C1") (pin "2") (pinfunction "2_2") (pintype "passive"))
      (node (ref "C10") (pin "1") (pinfunction "1_1") (pintype "passive"))
      (node (ref "C11") (pin "2") (pinfunction "2_2") (pintype "passive"))
      (node (ref "C12") (pin "2") (pinfunction "2_2") (pintype "passive"))
      (node (ref "C13") (pin "2") (pinfunction "2_2") (pintype "passive"))
      (node (ref "C14") (pin "2") (pinfunction "2_2") (pintype "passive"))
      (node (ref "C15") (pin "2") (pinfunction "2_2") (pintype "passive"))
      (node (ref "C2") (pin "2") (pinfunction "2_2") (pintype "passive"))
      (node (ref "C3") (pin "2") (pinfunction "2_2") (pintype "passive"))
      (node (ref "C4") (pin "2") (pinfunction "2_2") (pintype "passive"))
      (node (ref "C5") (pin "2") (pinfunction "2_2") (pintype "passive"))
      (node (ref "C6") (pin "2") (pinfunction "2_2") (pintype "passive"))
      (node (ref "C7") (pin "2") (pinfunction "2_2") (pintype "passive"))
      (node (ref "C8") (pin "2") (pinfunction "2_2") (pintype "passive"))
      (node (ref "C9") (pin "2") (pinfunction "2_2") (pintype "passive"))
      (node (ref "HC05") (pin "4") (pinfunction "4_4") (pintype "passive"))
      (node (ref "IC1") (pin "1") (pinfunction "GND/ADJ_1") (pintype "input"))
      (node (ref "IC2") (pin "1") (pinfunction "ADJ_1") (pintype "input"))
      (node (ref "IC3") (pin "11") (pinfunction "GND_11") (pintype "power_in"))
      (node (ref "IC3") (pin "32") (pinfunction "GND1_32") (pintype "power_in"))
      (node (ref "IC3") (pin "62") (pinfunction "GND2_62") (pintype "power_in"))
      (node (ref "IC3") (pin "81") (pinfunction "GND3_81") (pintype "power_in"))
      (node (ref "IC3") (pin "99") (pinfunction "AGND_99") (pintype "power_in"))
      (node (ref "IC4") (pin "2") (pinfunction "GND_2") (pintype "power_in"))
      (node (ref "IC5") (pin "2") (pinfunction "GND_2") (pintype "passive"))
      (node (ref "IC6") (pin "2") (pinfunction "GND_2") (pintype "passive"))
      (node (ref "J1") (pin "GND") (pinfunction "GND_GND") (pintype "bidirectional"))
      (node (ref "J1") (pin "GNDBREAK") (pinfunction "GNDBREAK_GNDBREAK") (pintype "bidirectional"))
      (node (ref "JP1") (pin "2") (pinfunction "2_2") (pintype "passive"))
      (node (ref "LED1") (pin "2") (pinfunction "2_2") (pintype "passive"))
      (node (ref "LED2") (pin "2") (pinfunction "2_2") (pintype "passive"))
      (node (ref "LED3") (pin "2") (pinfunction "2_2") (pintype "passive"))
      (node (ref "MPU") (pin "2") (pinfunction "2_2") (pintype "passive"))
      (node (ref "MPU") (pin "7") (pinfunction "7_7") (pintype "passive"))
      (node (ref "ON") (pin "K") (pinfunction "C_K") (pintype "passive"))
      (node (ref "PROGRAM") (pin "6") (pinfunction "6_6") (pintype "passive"))
      (node (ref "R13") (pin "1") (pinfunction "1_1") (pintype "passive"))
      (node (ref "R14") (pin "1") (pinfunction "1_1") (pintype "passive"))
      (node (ref "R15") (pin "1") (pinfunction "1_1") (pintype "passive"))
      (node (ref "RESET") (pin "1") (pinfunction "1_1") (pintype "passive"))
      (node (ref "RESET") (pin "2") (pinfunction "2_2") (pintype "passive"))
      (node (ref "SERV01") (pin "3") (pinfunction "3_3") (pintype "passive"))
      (node (ref "SERV02") (pin "3") (pinfunction "3_3") (pintype "passive"))
      (node (ref "SERV03") (pin "3") (pinfunction "3_3") (pintype "passive"))
      (node (ref "TMP102") (pin "1") (pinfunction "1_1") (pintype "passive"))
      (node (ref "TMP102") (pin "6") (pinfunction "6_6") (pintype "passive"))
      (node (ref "Y1") (pin "2") (pinfunction "2_2") (pintype "passive"))
    )
    (net (code "110") (name "Net-(ON-PadA)") (class "Default")
      (node (ref "ON") (pin "A") (pinfunction "A_A") (pintype "passive"))
      (node (ref "R1") (pin "2") (pinfunction "2_2") (pintype "passive"))
    )
    (net (code "111") (name "VCC") (class "Default")
      (node (ref "C1") (pin "1") (pinfunction "1_1") (pintype "passive"))
      (node (ref "C13") (pin "1") (pinfunction "1_1") (pintype "passive"))
      (node (ref "C14") (pin "1") (pinfunction "1_1") (pintype "passive"))
      (node (ref "C2") (pin "1") (pinfunction "1_1") (pintype "passive"))
      (node (ref "D1") (pin "C") (pinfunction "C_C") (pintype "passive"))
      (node (ref "IC1") (pin "3") (pinfunction "IN_3") (pintype "input"))
      (node (ref "IC2") (pin "3") (pinfunction "VI_3") (pintype "input"))
      (node (ref "IC5") (pin "1") (pinfunction "VI_1") (pintype "input"))
      (node (ref "IC6") (pin "1") (pinfunction "VI_1") (pintype "input"))
    )
    (net (code "112") (name "unconnected-(IC4-NC{slash}FB-Pad4)") (class "Default")
      (node (ref "IC4") (pin "4") (pinfunction "NC/FB_4") (pintype "passive"))
    )
  )
)
